# microbutton.net
KiCad netlist of a schematic drawn in EAGLE
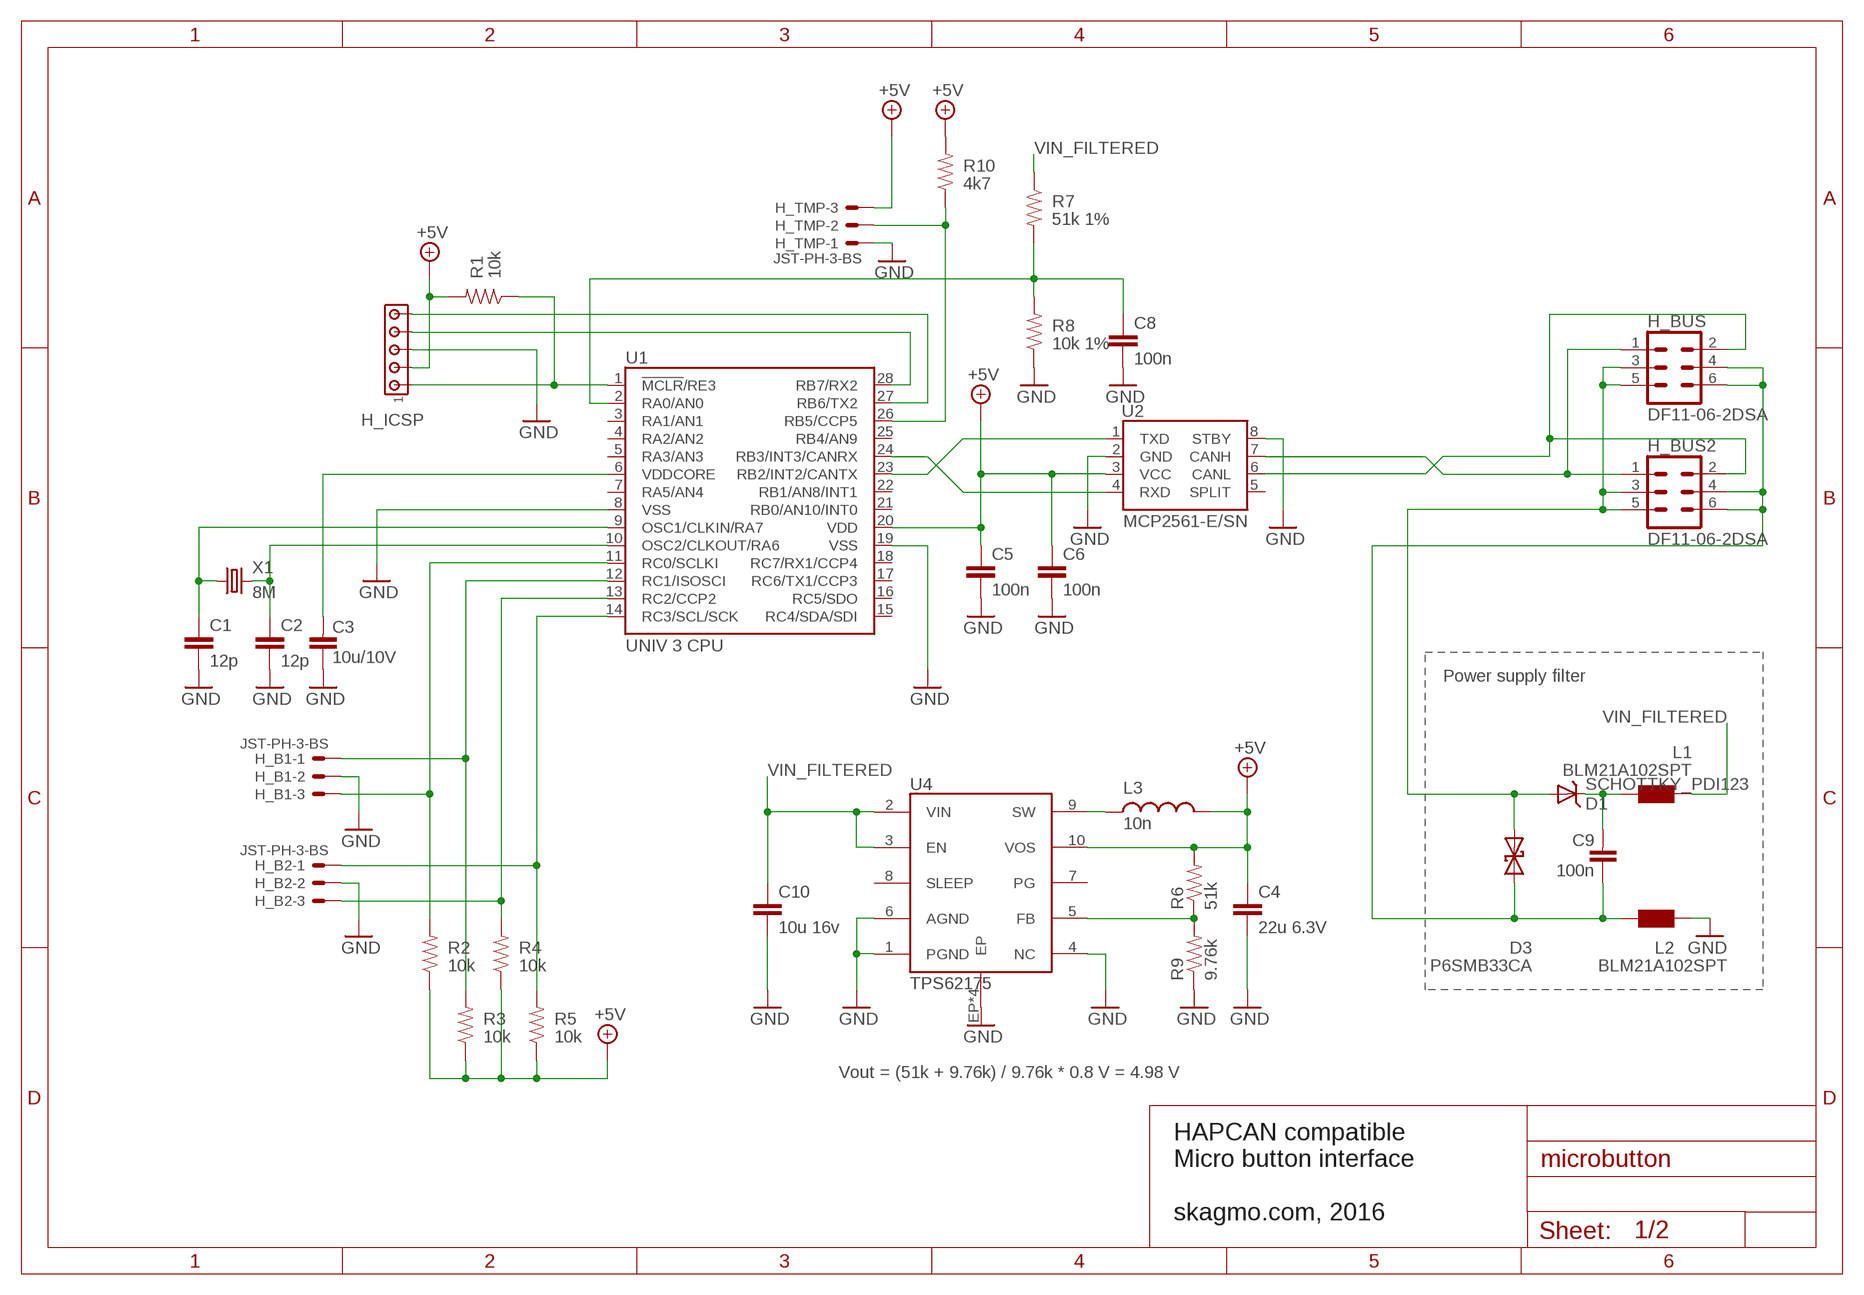
[diagram p0: schematic, sheet 1]

(export (version "E")
  (design (tool "Eeschema 10.0.6"))
  (components
    (comp (ref "C1")
      (value "12p")
      (footprint "eagle-import:0603")
      (libsource (lib "eagle-import") (part "CAP0603"))
    )
    (comp (ref "C2")
      (value "12p")
      (footprint "eagle-import:0603")
      (libsource (lib "eagle-import") (part "CAP0603"))
    )
    (comp (ref "C3")
      (value "10u/10V")
      (footprint "eagle-import:0805")
      (libsource (lib "eagle-import") (part "CAPACITOR0805"))
    )
    (comp (ref "C4")
      (value "22u 6.3V")
      (footprint "eagle-import:0805")
      (libsource (lib "eagle-import") (part "CAP0805"))
    )
    (comp (ref "C5")
      (value "100n")
      (footprint "eagle-import:0603")
      (libsource (lib "eagle-import") (part "CAP0603"))
    )
    (comp (ref "C6")
      (value "100n")
      (footprint "eagle-import:0603")
      (libsource (lib "eagle-import") (part "CAP0603"))
    )
    (comp (ref "C8")
      (value "100n")
      (footprint "eagle-import:0603")
      (libsource (lib "eagle-import") (part "CAP0603"))
    )
    (comp (ref "C9")
      (value "100n")
      (footprint "eagle-import:0805")
      (libsource (lib "eagle-import") (part "CAPACITOR0805"))
    )
    (comp (ref "C10")
      (value "10u 16v")
      (footprint "eagle-import:1206")
      (libsource (lib "eagle-import") (part "CAP1206"))
    )
    (comp (ref "D1")
      (value "SCHOTTKY_PDI123")
      (footprint "eagle-import:POWERDI123")
      (libsource (lib "eagle-import") (part "SCHOTTKY_PDI123"))
    )
    (comp (ref "D3")
      (value "P6SMB33CA")
      (footprint "eagle-import:DO-214_TRANSIL2")
      (libsource (lib "eagle-import") (part "DIODE_TRANSIL2"))
    )
    (comp (ref "H_B1")
      (value "JST-PH-3-BS")
      (footprint "eagle-import:B3B-PH-K-S")
      (libsource (lib "eagle-import") (part "JST-PH-3-BS"))
    )
    (comp (ref "H_B2")
      (value "JST-PH-3-BS")
      (footprint "eagle-import:B3B-PH-K-S")
      (libsource (lib "eagle-import") (part "JST-PH-3-BS"))
    )
    (comp (ref "H_BUS")
      (value "DF11-06-2DSA")
      (footprint "eagle-import:DF11-06DP-2DSA")
      (libsource (lib "eagle-import") (part "DF11-06-2DSA"))
    )
    (comp (ref "H_BUS2")
      (value "DF11-06-2DSA")
      (footprint "eagle-import:DF11-06DP-2DSA")
      (libsource (lib "eagle-import") (part "DF11-06-2DSA"))
    )
    (comp (ref "H_ICSP")
      (value "HEADER5")
      (footprint "eagle-import:SIP-5")
      (libsource (lib "eagle-import") (part "HEADER5"))
    )
    (comp (ref "H_TMP")
      (value "JST-PH-3-BS")
      (footprint "eagle-import:B3B-PH-K-S")
      (libsource (lib "eagle-import") (part "JST-PH-3-BS"))
    )
    (comp (ref "L1")
      (value "BLM21A102SPT")
      (footprint "eagle-import:0805")
      (libsource (lib "eagle-import") (part "CHOKE0805"))
    )
    (comp (ref "L2")
      (value "BLM21A102SPT")
      (footprint "eagle-import:0805")
      (libsource (lib "eagle-import") (part "CHOKE0805"))
    )
    (comp (ref "L3")
      (value "10n")
      (footprint "eagle-import:IND-SRN3015")
      (libsource (lib "eagle-import") (part "INDUCTOR_SRN3015"))
    )
    (comp (ref "R1")
      (value "10k")
      (footprint "eagle-import:0603")
      (libsource (lib "eagle-import") (part "RESISTOR0603"))
    )
    (comp (ref "R2")
      (value "10k")
      (footprint "eagle-import:0603")
      (libsource (lib "eagle-import") (part "RESISTOR0603"))
    )
    (comp (ref "R3")
      (value "10k")
      (footprint "eagle-import:0603")
      (libsource (lib "eagle-import") (part "RESISTOR0603"))
    )
    (comp (ref "R4")
      (value "10k")
      (footprint "eagle-import:0603")
      (libsource (lib "eagle-import") (part "RESISTOR0603"))
    )
    (comp (ref "R5")
      (value "10k")
      (footprint "eagle-import:0603")
      (libsource (lib "eagle-import") (part "RESISTOR0603"))
    )
    (comp (ref "R6")
      (value "51k")
      (footprint "eagle-import:0603")
      (libsource (lib "eagle-import") (part "RESISTOR0603"))
    )
    (comp (ref "R7")
      (value "51k 1%")
      (footprint "eagle-import:0603")
      (libsource (lib "eagle-import") (part "RESISTOR0603"))
    )
    (comp (ref "R8")
      (value "10k 1%")
      (footprint "eagle-import:0603")
      (libsource (lib "eagle-import") (part "RESISTOR0603"))
    )
    (comp (ref "R9")
      (value "9.76k")
      (footprint "eagle-import:0603")
      (libsource (lib "eagle-import") (part "RESISTOR0603"))
    )
    (comp (ref "R10")
      (value "4k7")
      (footprint "eagle-import:0603")
      (libsource (lib "eagle-import") (part "RESISTOR0603"))
    )
    (comp (ref "U1")
      (value "UNIV 3 CPU")
      (footprint "eagle-import:UNIV3CPU")
      (libsource (lib "eagle-import") (part "UNIV3CPU"))
    )
    (comp (ref "U2")
      (value "MCP2561-E/SN")
      (footprint "eagle-import:SO-08")
      (libsource (lib "eagle-import") (part "MCP2561-E/SN"))
    )
    (comp (ref "U4")
      (value "TPS62175")
      (footprint "eagle-import:WSON-10")
      (libsource (lib "eagle-import") (part "TPS62175"))
    )
    (comp (ref "X1")
      (value "8M")
      (footprint "eagle-import:TXC-7A_HAND")
      (libsource (lib "eagle-import") (part "CRYSTAL_HAND"))
    )
  )
  (nets
    (net (code "1") (name "+5V") (class "Default")
      (node (ref "C4") (pin "1") (pinfunction "1_1") (pintype "passive"))
      (node (ref "C5") (pin "1") (pinfunction "1_1") (pintype "passive"))
      (node (ref "C6") (pin "1") (pinfunction "1_1") (pintype "passive"))
      (node (ref "H_ICSP") (pin "2") (pinfunction "2_2") (pintype "passive"))
      (node (ref "H_TMP") (pin "3") (pinfunction "S_3") (pintype "passive"))
      (node (ref "L3") (pin "P$2") (pinfunction "2_P$2") (pintype "passive"))
      (node (ref "R1") (pin "2") (pinfunction "2_2") (pintype "passive"))
      (node (ref "R10") (pin "2") (pinfunction "2_2") (pintype "passive"))
      (node (ref "R2") (pin "1") (pinfunction "1_1") (pintype "passive"))
      (node (ref "R3") (pin "1") (pinfunction "1_1") (pintype "passive"))
      (node (ref "R4") (pin "1") (pinfunction "1_1") (pintype "passive"))
      (node (ref "R5") (pin "1") (pinfunction "1_1") (pintype "passive"))
      (node (ref "R6") (pin "2") (pinfunction "2_2") (pintype "passive"))
      (node (ref "U1") (pin "20") (pinfunction "VDD_20") (pintype "bidirectional"))
      (node (ref "U2") (pin "3") (pinfunction "VCC_3") (pintype "bidirectional"))
      (node (ref "U4") (pin "10") (pinfunction "VOS_10") (pintype "bidirectional"))
    )
    (net (code "2") (name "GND") (class "Default")
      (node (ref "C1") (pin "2") (pinfunction "2_2") (pintype "passive"))
      (node (ref "C10") (pin "2") (pinfunction "2_2") (pintype "passive"))
      (node (ref "C2") (pin "2") (pinfunction "2_2") (pintype "passive"))
      (node (ref "C3") (pin "2") (pinfunction "2_2") (pintype "passive"))
      (node (ref "C4") (pin "2") (pinfunction "2_2") (pintype "passive"))
      (node (ref "C5") (pin "2") (pinfunction "2_2") (pintype "passive"))
      (node (ref "C6") (pin "2") (pinfunction "2_2") (pintype "passive"))
      (node (ref "C8") (pin "2") (pinfunction "2_2") (pintype "passive"))
      (node (ref "H_B1") (pin "2") (pinfunction "S_2") (pintype "passive"))
      (node (ref "H_B2") (pin "2") (pinfunction "S_2") (pintype "passive"))
      (node (ref "H_ICSP") (pin "3") (pinfunction "3_3") (pintype "passive"))
      (node (ref "H_TMP") (pin "1") (pinfunction "S_1") (pintype "passive"))
      (node (ref "L2") (pin "1") (pinfunction "1_1") (pintype "passive"))
      (node (ref "R8") (pin "1") (pinfunction "1_1") (pintype "passive"))
      (node (ref "R9") (pin "1") (pinfunction "1_1") (pintype "passive"))
      (node (ref "U1") (pin "19") (pinfunction "VSS_19") (pintype "bidirectional"))
      (node (ref "U1") (pin "8") (pinfunction "VSS_8") (pintype "bidirectional"))
      (node (ref "U2") (pin "2") (pinfunction "GND_2") (pintype "bidirectional"))
      (node (ref "U2") (pin "8") (pinfunction "STBY_8") (pintype "bidirectional"))
      (node (ref "U4") (pin "1") (pinfunction "PGND_1") (pintype "bidirectional"))
      (node (ref "U4") (pin "4") (pinfunction "NC_4") (pintype "bidirectional"))
      (node (ref "U4") (pin "6") (pinfunction "AGND_6") (pintype "bidirectional"))
      (node (ref "U4") (pin "EP") (pinfunction "EP_EP") (pintype "bidirectional"))
      (node (ref "U4") (pin "V1") (pinfunction "EP_V1") (pintype "bidirectional"))
      (node (ref "U4") (pin "V2") (pinfunction "EP_V2") (pintype "bidirectional"))
      (node (ref "U4") (pin "V3") (pinfunction "EP_V3") (pintype "bidirectional"))
    )
    (net (code "3") (name "Net-(C9-Pad1)") (class "Default")
      (node (ref "C9") (pin "1") (pinfunction "1_1") (pintype "passive"))
      (node (ref "D1") (pin "C") (pinfunction "C_C") (pintype "passive"))
      (node (ref "L1") (pin "2") (pinfunction "2_2") (pintype "passive"))
    )
    (net (code "4") (name "Net-(D3-1)") (class "Default")
      (node (ref "C9") (pin "2") (pinfunction "2_2") (pintype "passive"))
      (node (ref "D3") (pin "A") (pinfunction "1_A") (pintype "passive"))
      (node (ref "H_BUS") (pin "4") (pinfunction "4_4") (pintype "passive"))
      (node (ref "H_BUS") (pin "6") (pinfunction "6_6") (pintype "passive"))
      (node (ref "H_BUS2") (pin "4") (pinfunction "4_4") (pintype "passive"))
      (node (ref "H_BUS2") (pin "6") (pinfunction "6_6") (pintype "passive"))
      (node (ref "L2") (pin "2") (pinfunction "2_2") (pintype "passive"))
    )
    (net (code "5") (name "Net-(D3-2)") (class "Default")
      (node (ref "D1") (pin "A") (pinfunction "A_A") (pintype "passive"))
      (node (ref "D3") (pin "C") (pinfunction "2_C") (pintype "passive"))
      (node (ref "H_BUS") (pin "3") (pinfunction "3_3") (pintype "passive"))
      (node (ref "H_BUS") (pin "5") (pinfunction "5_5") (pintype "passive"))
      (node (ref "H_BUS2") (pin "3") (pinfunction "3_3") (pintype "passive"))
      (node (ref "H_BUS2") (pin "5") (pinfunction "5_5") (pintype "passive"))
    )
    (net (code "6") (name "Net-(H_B1A-S)") (class "Default")
      (node (ref "H_B1") (pin "1") (pinfunction "S_1") (pintype "passive"))
      (node (ref "R3") (pin "2") (pinfunction "2_2") (pintype "passive"))
      (node (ref "U1") (pin "12") (pinfunction "RC1/ISOSCI_12") (pintype "bidirectional"))
    )
    (net (code "7") (name "Net-(H_B1C-S)") (class "Default")
      (node (ref "H_B1") (pin "3") (pinfunction "S_3") (pintype "passive"))
      (node (ref "R2") (pin "2") (pinfunction "2_2") (pintype "passive"))
      (node (ref "U1") (pin "11") (pinfunction "RC0/SCLKI_11") (pintype "bidirectional"))
    )
    (net (code "8") (name "Net-(H_B2A-S)") (class "Default")
      (node (ref "H_B2") (pin "1") (pinfunction "S_1") (pintype "passive"))
      (node (ref "R5") (pin "2") (pinfunction "2_2") (pintype "passive"))
      (node (ref "U1") (pin "14") (pinfunction "RC3/SCL/SCK_14") (pintype "bidirectional"))
    )
    (net (code "9") (name "Net-(H_B2C-S)") (class "Default")
      (node (ref "H_B2") (pin "3") (pinfunction "S_3") (pintype "passive"))
      (node (ref "R4") (pin "2") (pinfunction "2_2") (pintype "passive"))
      (node (ref "U1") (pin "13") (pinfunction "RC2/CCP2_13") (pintype "bidirectional"))
    )
    (net (code "10") (name "Net-(H_TMPB-S)") (class "Default")
      (node (ref "H_TMP") (pin "2") (pinfunction "S_2") (pintype "passive"))
      (node (ref "R10") (pin "1") (pinfunction "1_1") (pintype "passive"))
      (node (ref "U1") (pin "26") (pinfunction "RB5/CCP5_26") (pintype "bidirectional"))
    )
    (net (code "11") (name "Net-(L3-1)") (class "Default")
      (node (ref "L3") (pin "P$1") (pinfunction "1_P$1") (pintype "passive"))
      (node (ref "U4") (pin "9") (pinfunction "SW_9") (pintype "bidirectional"))
    )
    (net (code "12") (name "Net-(U1-OSC1{slash}CLKIN{slash}RA7)") (class "Default")
      (node (ref "C1") (pin "1") (pinfunction "1_1") (pintype "passive"))
      (node (ref "U1") (pin "9") (pinfunction "OSC1/CLKIN/RA7_9") (pintype "bidirectional"))
      (node (ref "X1") (pin "1") (pinfunction "1_1") (pintype "passive"))
    )
    (net (code "13") (name "Net-(U1-OSC2{slash}CLKOUT{slash}RA6)") (class "Default")
      (node (ref "C2") (pin "1") (pinfunction "1_1") (pintype "passive"))
      (node (ref "U1") (pin "10") (pinfunction "OSC2/CLKOUT/RA6_10") (pintype "bidirectional"))
      (node (ref "X1") (pin "2") (pinfunction "2_2") (pintype "passive"))
    )
    (net (code "14") (name "Net-(U1-RA0{slash}AN0)") (class "Default")
      (node (ref "C8") (pin "1") (pinfunction "1_1") (pintype "passive"))
      (node (ref "R7") (pin "2") (pinfunction "2_2") (pintype "passive"))
      (node (ref "R8") (pin "2") (pinfunction "2_2") (pintype "passive"))
      (node (ref "U1") (pin "2") (pinfunction "RA0/AN0_2") (pintype "bidirectional"))
    )
    (net (code "15") (name "Net-(U1-RB2{slash}INT2{slash}CANTX)") (class "Default")
      (node (ref "U1") (pin "23") (pinfunction "RB2/INT2/CANTX_23") (pintype "bidirectional"))
      (node (ref "U2") (pin "1") (pinfunction "TXD_1") (pintype "bidirectional"))
    )
    (net (code "16") (name "Net-(U1-RB3{slash}INT3{slash}CANRX)") (class "Default")
      (node (ref "U1") (pin "24") (pinfunction "RB3/INT3/CANRX_24") (pintype "bidirectional"))
      (node (ref "U2") (pin "4") (pinfunction "RXD_4") (pintype "bidirectional"))
    )
    (net (code "17") (name "Net-(U1-RB6{slash}TX2)") (class "Default")
      (node (ref "H_ICSP") (pin "5") (pinfunction "5_5") (pintype "passive"))
      (node (ref "U1") (pin "27") (pinfunction "RB6/TX2_27") (pintype "bidirectional"))
    )
    (net (code "18") (name "Net-(U1-RB7{slash}RX2)") (class "Default")
      (node (ref "H_ICSP") (pin "4") (pinfunction "4_4") (pintype "passive"))
      (node (ref "U1") (pin "28") (pinfunction "RB7/RX2_28") (pintype "bidirectional"))
    )
    (net (code "19") (name "Net-(U1-VDDCORE)") (class "Default")
      (node (ref "C3") (pin "1") (pinfunction "1_1") (pintype "passive"))
      (node (ref "U1") (pin "6") (pinfunction "VDDCORE_6") (pintype "bidirectional"))
    )
    (net (code "20") (name "Net-(U1-~{MCLR}{slash}RE3)") (class "Default")
      (node (ref "H_ICSP") (pin "1") (pinfunction "1_1") (pintype "passive"))
      (node (ref "R1") (pin "1") (pinfunction "1_1") (pintype "passive"))
      (node (ref "U1") (pin "1") (pinfunction "~{MCLR}/RE3_1") (pintype "bidirectional"))
    )
    (net (code "21") (name "Net-(U2-CANH)") (class "Default")
      (node (ref "H_BUS") (pin "1") (pinfunction "1_1") (pintype "passive"))
      (node (ref "H_BUS2") (pin "1") (pinfunction "1_1") (pintype "passive"))
      (node (ref "U2") (pin "7") (pinfunction "CANH_7") (pintype "bidirectional"))
    )
    (net (code "22") (name "Net-(U2-CANL)") (class "Default")
      (node (ref "H_BUS") (pin "2") (pinfunction "2_2") (pintype "passive"))
      (node (ref "H_BUS2") (pin "2") (pinfunction "2_2") (pintype "passive"))
      (node (ref "U2") (pin "6") (pinfunction "CANL_6") (pintype "bidirectional"))
    )
    (net (code "23") (name "Net-(U4-FB)") (class "Default")
      (node (ref "R6") (pin "1") (pinfunction "1_1") (pintype "passive"))
      (node (ref "R9") (pin "2") (pinfunction "2_2") (pintype "passive"))
      (node (ref "U4") (pin "5") (pinfunction "FB_5") (pintype "bidirectional"))
    )
    (net (code "24") (name "VIN_FILTERED") (class "Default")
      (node (ref "C10") (pin "1") (pinfunction "1_1") (pintype "passive"))
      (node (ref "L1") (pin "1") (pinfunction "1_1") (pintype "passive"))
      (node (ref "R7") (pin "1") (pinfunction "1_1") (pintype "passive"))
      (node (ref "U4") (pin "2") (pinfunction "VIN_2") (pintype "bidirectional"))
      (node (ref "U4") (pin "3") (pinfunction "EN_3") (pintype "bidirectional"))
    )
    (net (code "25") (name "unconnected-(U1-RA1{slash}AN1-Pad3)") (class "Default")
      (node (ref "U1") (pin "3") (pinfunction "RA1/AN1_3") (pintype "bidirectional"))
    )
    (net (code "26") (name "unconnected-(U1-RA2{slash}AN2-Pad4)") (class "Default")
      (node (ref "U1") (pin "4") (pinfunction "RA2/AN2_4") (pintype "bidirectional"))
    )
    (net (code "27") (name "unconnected-(U1-RA3{slash}AN3-Pad5)") (class "Default")
      (node (ref "U1") (pin "5") (pinfunction "RA3/AN3_5") (pintype "bidirectional"))
    )
    (net (code "28") (name "unconnected-(U1-RA5{slash}AN4-Pad7)") (class "Default")
      (node (ref "U1") (pin "7") (pinfunction "RA5/AN4_7") (pintype "bidirectional"))
    )
    (net (code "29") (name "unconnected-(U1-RB0{slash}AN10{slash}INT0-Pad21)") (class "Default")
      (node (ref "U1") (pin "21") (pinfunction "RB0/AN10/INT0_21") (pintype "bidirectional"))
    )
    (net (code "30") (name "unconnected-(U1-RB1{slash}AN8{slash}INT1-Pad22)") (class "Default")
      (node (ref "U1") (pin "22") (pinfunction "RB1/AN8/INT1_22") (pintype "bidirectional"))
    )
    (net (code "31") (name "unconnected-(U1-RB4{slash}AN9-Pad25)") (class "Default")
      (node (ref "U1") (pin "25") (pinfunction "RB4/AN9_25") (pintype "bidirectional"))
    )
    (net (code "32") (name "unconnected-(U1-RC4{slash}SDA{slash}SDI-Pad15)") (class "Default")
      (node (ref "U1") (pin "15") (pinfunction "RC4/SDA/SDI_15") (pintype "bidirectional"))
    )
    (net (code "33") (name "unconnected-(U1-RC5{slash}SDO-Pad16)") (class "Default")
      (node (ref "U1") (pin "16") (pinfunction "RC5/SDO_16") (pintype "bidirectional"))
    )
    (net (code "34") (name "unconnected-(U1-RC6{slash}TX1{slash}CCP3-Pad17)") (class "Default")
      (node (ref "U1") (pin "17") (pinfunction "RC6/TX1/CCP3_17") (pintype "bidirectional"))
    )
    (net (code "35") (name "unconnected-(U1-RC7{slash}RX1{slash}CCP4-Pad18)") (class "Default")
      (node (ref "U1") (pin "18") (pinfunction "RC7/RX1/CCP4_18") (pintype "bidirectional"))
    )
    (net (code "36") (name "unconnected-(U2-SPLIT-Pad5)") (class "Default")
      (node (ref "U2") (pin "5") (pinfunction "SPLIT_5") (pintype "bidirectional"))
    )
    (net (code "37") (name "unconnected-(U4-PG-Pad7)") (class "Default")
      (node (ref "U4") (pin "7") (pinfunction "PG_7") (pintype "bidirectional"))
    )
    (net (code "38") (name "unconnected-(U4-SLEEP-Pad8)") (class "Default")
      (node (ref "U4") (pin "8") (pinfunction "SLEEP_8") (pintype "bidirectional"))
    )
  )
)
